# LSN50_v3_0.net
KiCad netlist of a schematic drawn in EAGLE
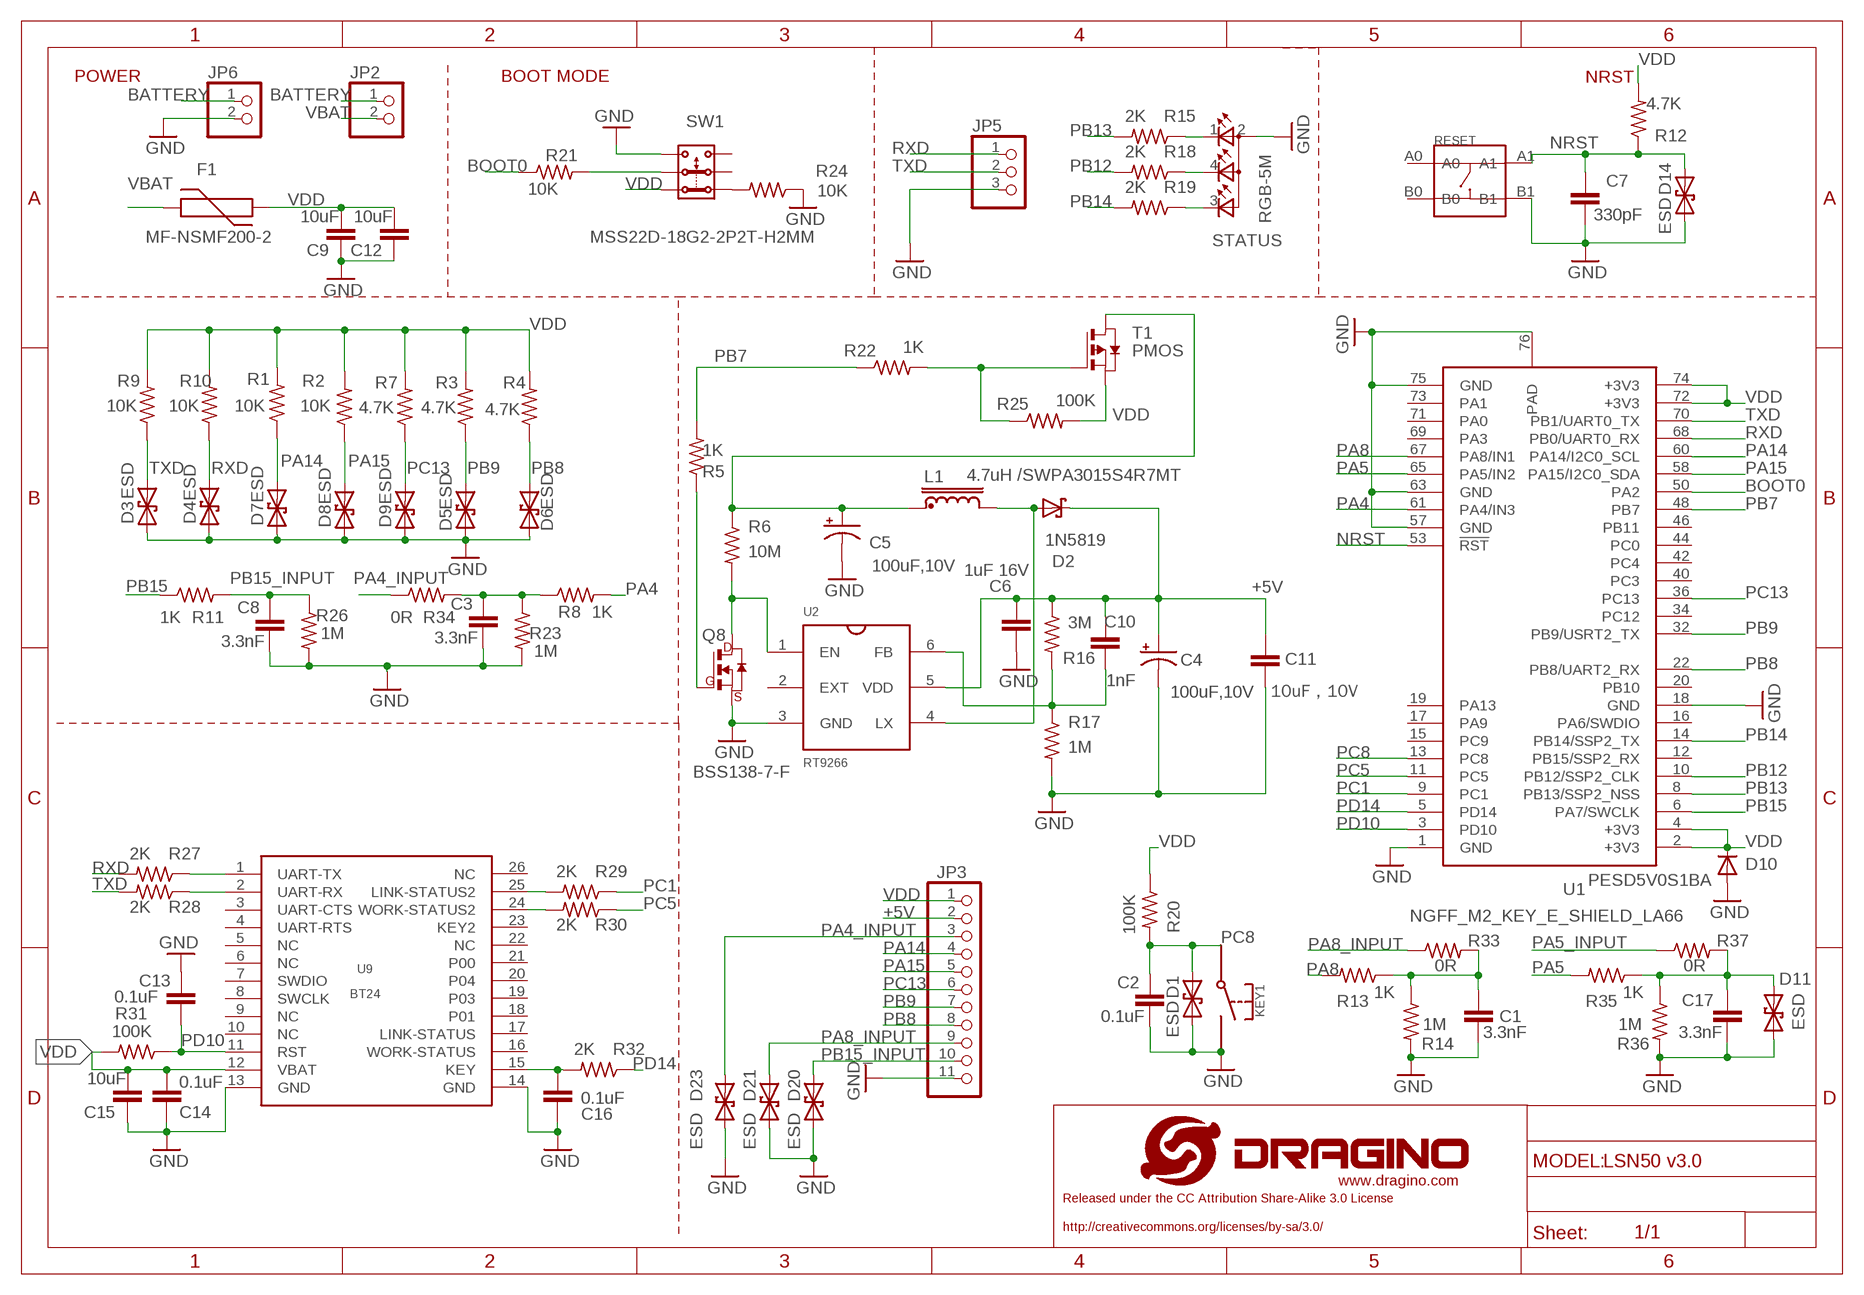
[diagram p0: schematic, sheet 1]

(export (version "E")
  (design (tool "Eeschema 10.0.6"))
  (components
    (comp (ref "C1")
      (value "3.3nF")
      (footprint "eagle-import:C0402")
      (libsource (lib "eagle-import") (part "C-EUC0402"))
    )
    (comp (ref "C2")
      (value "0.1uF")
      (footprint "eagle-import:C0402")
      (libsource (lib "eagle-import") (part "C-EUC0402"))
    )
    (comp (ref "C3")
      (value "3.3nF")
      (footprint "eagle-import:C0402")
      (libsource (lib "eagle-import") (part "C-EUC0402"))
    )
    (comp (ref "C4")
      (value "100uF,10V")
      (footprint "eagle-import:SMC_B")
      (libsource (lib "eagle-import") (part "CPOL-USSMCB"))
    )
    (comp (ref "C5")
      (value "100uF,10V")
      (footprint "eagle-import:SMC_B")
      (libsource (lib "eagle-import") (part "CPOL-USSMCB"))
    )
    (comp (ref "C6")
      (value "1uF 16V")
      (footprint "eagle-import:C0603")
      (libsource (lib "eagle-import") (part "C-EUC0603"))
    )
    (comp (ref "C7")
      (value "330pF")
      (footprint "eagle-import:C0402")
      (libsource (lib "eagle-import") (part "C-EUC0402"))
    )
    (comp (ref "C8")
      (value "3.3nF")
      (footprint "eagle-import:C0402")
      (libsource (lib "eagle-import") (part "C-EUC0402"))
    )
    (comp (ref "C9")
      (value "10uF")
      (footprint "eagle-import:C0805")
      (libsource (lib "eagle-import") (part "C-EUC0805"))
    )
    (comp (ref "C10")
      (value "1nF")
      (footprint "eagle-import:C0402")
      (libsource (lib "eagle-import") (part "C-EUC0402"))
    )
    (comp (ref "C11")
      (value "10uF，10V")
      (footprint "eagle-import:C0805")
      (libsource (lib "eagle-import") (part "dragino-passive_C-EUC0805"))
    )
    (comp (ref "C12")
      (value "10uF")
      (footprint "eagle-import:C0805")
      (libsource (lib "eagle-import") (part "C-EUC0805"))
    )
    (comp (ref "C13")
      (value "0.1uF")
      (footprint "eagle-import:C0402")
      (libsource (lib "eagle-import") (part "C-EUC0402"))
    )
    (comp (ref "C14")
      (value "0.1uF")
      (footprint "eagle-import:C0402")
      (libsource (lib "eagle-import") (part "C-EUC0402"))
    )
    (comp (ref "C15")
      (value "10uF")
      (footprint "eagle-import:C0805")
      (libsource (lib "eagle-import") (part "C-EUC0805"))
    )
    (comp (ref "C16")
      (value "0.1uF")
      (footprint "eagle-import:C0402")
      (libsource (lib "eagle-import") (part "C-EUC0402"))
    )
    (comp (ref "C17")
      (value "3.3nF")
      (footprint "eagle-import:C0402")
      (libsource (lib "eagle-import") (part "C-EUC0402"))
    )
    (comp (ref "D1")
      (value "ESD")
      (footprint "eagle-import:DFN1006")
      (libsource (lib "eagle-import") (part "ESD_TVS"))
    )
    (comp (ref "D2")
      (value "1N5819")
      (footprint "eagle-import:SOD123FL")
      (libsource (lib "eagle-import") (part "SMF5.0AT1"))
    )
    (comp (ref "D3")
      (value "ESD")
      (footprint "eagle-import:DFN1006")
      (libsource (lib "eagle-import") (part "ESD_TVS"))
    )
    (comp (ref "D4")
      (value "ESD")
      (footprint "eagle-import:DFN1006")
      (libsource (lib "eagle-import") (part "ESD_TVS"))
    )
    (comp (ref "D5")
      (value "ESD")
      (footprint "eagle-import:DFN1006")
      (libsource (lib "eagle-import") (part "ESD_TVS"))
    )
    (comp (ref "D6")
      (value "ESD")
      (footprint "eagle-import:DFN1006")
      (libsource (lib "eagle-import") (part "ESD_TVS"))
    )
    (comp (ref "D7")
      (value "ESD")
      (footprint "eagle-import:DFN1006")
      (libsource (lib "eagle-import") (part "ESD_TVS"))
    )
    (comp (ref "D8")
      (value "ESD")
      (footprint "eagle-import:DFN1006")
      (libsource (lib "eagle-import") (part "ESD_TVS"))
    )
    (comp (ref "D9")
      (value "ESD")
      (footprint "eagle-import:DFN1006")
      (libsource (lib "eagle-import") (part "ESD_TVS"))
    )
    (comp (ref "D10")
      (value "PESD5V0S1BA")
      (footprint "eagle-import:DIODE_SOD323-R")
      (libsource (lib "eagle-import") (part "DIODESOD323-R"))
    )
    (comp (ref "D11")
      (value "ESD")
      (footprint "eagle-import:DFN1006")
      (libsource (lib "eagle-import") (part "ESD_TVS"))
    )
    (comp (ref "D14")
      (value "ESD")
      (footprint "eagle-import:DFN1006")
      (libsource (lib "eagle-import") (part "ESD_TVS"))
    )
    (comp (ref "D20")
      (value "ESD")
      (footprint "eagle-import:DFN1006")
      (libsource (lib "eagle-import") (part "ESD_TVS"))
    )
    (comp (ref "D21")
      (value "ESD")
      (footprint "eagle-import:DFN1006")
      (libsource (lib "eagle-import") (part "ESD_TVS"))
    )
    (comp (ref "D23")
      (value "ESD")
      (footprint "eagle-import:DFN1006")
      (libsource (lib "eagle-import") (part "ESD_TVS"))
    )
    (comp (ref "F1")
      (value "MF-NSMF200-2")
      (footprint "eagle-import:R1206")
      (libsource (lib "eagle-import") (part "FUSE1206"))
    )
    (comp (ref "JP2")
      (value "PINHD-1X2")
      (footprint "eagle-import:1X02")
      (libsource (lib "eagle-import") (part "PINHD-1X2"))
    )
    (comp (ref "JP3")
      (value "PINHD-1X11-MM")
      (footprint "eagle-import:KF350-11P")
      (libsource (lib "eagle-import") (part "PINHD-1X11-MM"))
    )
    (comp (ref "JP5")
      (value "PINHD-1X3")
      (footprint "eagle-import:1X03")
      (libsource (lib "eagle-import") (part "PINHD-1X3"))
    )
    (comp (ref "JP6")
      (value "PINHD-1X2\"\"")
      (footprint "eagle-import:XH2.54-2P")
      (libsource (lib "eagle-import") (part "PINHD-1X2{dblquote}{dblquote}"))
    )
    (comp (ref "KEY1")
      (value "SWITCHDIL4")
      (footprint "eagle-import:SWITCH_6X6X19_DIL4")
      (libsource (lib "eagle-import") (part "SWITCHDIL4"))
    )
    (comp (ref "L1")
      (value "4.7uH /SWPA3015S4R7MT")
      (footprint "eagle-import:SWPA3010S")
      (libsource (lib "eagle-import") (part "INDUCTORSWPA3010S"))
    )
    (comp (ref "Q8")
      (value "BSS138-7-F")
      (footprint "eagle-import:SOT-23")
      (libsource (lib "eagle-import") (part "NMOSFET"))
    )
    (comp (ref "R1")
      (value "10K")
      (footprint "eagle-import:R0402")
      (libsource (lib "eagle-import") (part "R-US_R0402"))
    )
    (comp (ref "R2")
      (value "10K")
      (footprint "eagle-import:R0402")
      (libsource (lib "eagle-import") (part "R-US_R0402"))
    )
    (comp (ref "R3")
      (value "4.7K")
      (footprint "eagle-import:R0402")
      (libsource (lib "eagle-import") (part "R-US_R0402"))
    )
    (comp (ref "R4")
      (value "4.7K")
      (footprint "eagle-import:R0402")
      (libsource (lib "eagle-import") (part "R-US_R0402"))
    )
    (comp (ref "R5")
      (value "1K")
      (footprint "eagle-import:R0402")
      (libsource (lib "eagle-import") (part "R-US_R0402"))
    )
    (comp (ref "R6")
      (value "10M")
      (footprint "eagle-import:R0402")
      (libsource (lib "eagle-import") (part "R-US_R0402"))
    )
    (comp (ref "R7")
      (value "4.7K")
      (footprint "eagle-import:R0402")
      (libsource (lib "eagle-import") (part "R-US_R0402"))
    )
    (comp (ref "R8")
      (value "1K")
      (footprint "eagle-import:R0402")
      (libsource (lib "eagle-import") (part "R-US_R0402"))
    )
    (comp (ref "R9")
      (value "10K")
      (footprint "eagle-import:R0402")
      (libsource (lib "eagle-import") (part "R-US_R0402"))
    )
    (comp (ref "R10")
      (value "10K")
      (footprint "eagle-import:R0402")
      (libsource (lib "eagle-import") (part "R-US_R0402"))
    )
    (comp (ref "R11")
      (value "1K")
      (footprint "eagle-import:R0402")
      (libsource (lib "eagle-import") (part "R-US_R0402"))
    )
    (comp (ref "R12")
      (value "4.7K")
      (footprint "eagle-import:R0402")
      (libsource (lib "eagle-import") (part "R-US_R0402"))
    )
    (comp (ref "R13")
      (value "1K")
      (footprint "eagle-import:R0402")
      (libsource (lib "eagle-import") (part "R-US_R0402"))
    )
    (comp (ref "R14")
      (value "1M")
      (footprint "eagle-import:R0402")
      (libsource (lib "eagle-import") (part "R-US_R0402"))
    )
    (comp (ref "R15")
      (value "2K")
      (footprint "eagle-import:R0402")
      (libsource (lib "eagle-import") (part "R-US_R0402"))
    )
    (comp (ref "R16")
      (value "3M")
      (footprint "eagle-import:R0402")
      (libsource (lib "eagle-import") (part "R-US_R0402"))
    )
    (comp (ref "R17")
      (value "1M")
      (footprint "eagle-import:R0402")
      (libsource (lib "eagle-import") (part "R-US_R0402"))
    )
    (comp (ref "R18")
      (value "2K")
      (footprint "eagle-import:R0402")
      (libsource (lib "eagle-import") (part "R-US_R0402"))
    )
    (comp (ref "R19")
      (value "2K")
      (footprint "eagle-import:R0402")
      (libsource (lib "eagle-import") (part "R-US_R0402"))
    )
    (comp (ref "R20")
      (value "100K")
      (footprint "eagle-import:R0402")
      (libsource (lib "eagle-import") (part "R-US_R0402"))
    )
    (comp (ref "R21")
      (value "10K")
      (footprint "eagle-import:R0402")
      (libsource (lib "eagle-import") (part "R-US_R0402"))
    )
    (comp (ref "R22")
      (value "1K")
      (footprint "eagle-import:R0402")
      (libsource (lib "eagle-import") (part "R-US_R0402"))
    )
    (comp (ref "R23")
      (value "1M")
      (footprint "eagle-import:R0402")
      (libsource (lib "eagle-import") (part "R-US_R0402"))
    )
    (comp (ref "R24")
      (value "10K")
      (footprint "eagle-import:R0402")
      (libsource (lib "eagle-import") (part "R-US_R0402"))
    )
    (comp (ref "R25")
      (value "100K")
      (footprint "eagle-import:R0402")
      (libsource (lib "eagle-import") (part "R-US_R0402"))
    )
    (comp (ref "R26")
      (value "1M")
      (footprint "eagle-import:R0402")
      (libsource (lib "eagle-import") (part "R-US_R0402"))
    )
    (comp (ref "R27")
      (value "2K")
      (footprint "eagle-import:R0402")
      (libsource (lib "eagle-import") (part "R-US_R0402"))
    )
    (comp (ref "R28")
      (value "2K")
      (footprint "eagle-import:R0402")
      (libsource (lib "eagle-import") (part "R-US_R0402"))
    )
    (comp (ref "R29")
      (value "2K")
      (footprint "eagle-import:R0402")
      (libsource (lib "eagle-import") (part "R-US_R0402"))
    )
    (comp (ref "R30")
      (value "2K")
      (footprint "eagle-import:R0402")
      (libsource (lib "eagle-import") (part "R-US_R0402"))
    )
    (comp (ref "R31")
      (value "100K")
      (footprint "eagle-import:R0402")
      (libsource (lib "eagle-import") (part "R-US_R0402"))
    )
    (comp (ref "R32")
      (value "2K")
      (footprint "eagle-import:R0402")
      (libsource (lib "eagle-import") (part "R-US_R0402"))
    )
    (comp (ref "R33")
      (value "0R")
      (footprint "eagle-import:R0402")
      (libsource (lib "eagle-import") (part "R-US_R0402"))
    )
    (comp (ref "R34")
      (value "0R")
      (footprint "eagle-import:R0402")
      (libsource (lib "eagle-import") (part "R-US_R0402"))
    )
    (comp (ref "R35")
      (value "1K")
      (footprint "eagle-import:R0402")
      (libsource (lib "eagle-import") (part "R-US_R0402"))
    )
    (comp (ref "R36")
      (value "1M")
      (footprint "eagle-import:R0402")
      (libsource (lib "eagle-import") (part "R-US_R0402"))
    )
    (comp (ref "R37")
      (value "0R")
      (footprint "eagle-import:R0402")
      (libsource (lib "eagle-import") (part "R-US_R0402"))
    )
    (comp (ref "RESET")
      (value "轻触开关3*3*1.5四脚贴片开关")
      (footprint "eagle-import:SW4-SMD-3.35X3.35X1.5MM")
      (libsource (lib "eagle-import") (part "BUTTON-4P-3.3X3.3"))
    )
    (comp (ref "STATUS")
      (value "RGB-5M")
      (footprint "eagle-import:RGB")
      (libsource (lib "eagle-import") (part "RGB-5M"))
    )
    (comp (ref "SW1")
      (value "MSS22D-18G2-2P2T-H2MM")
      (footprint "eagle-import:MSS22D-18G2-2P2T-H2MM-DIL")
      (libsource (lib "eagle-import") (part "MSS22D-18G2-2P2T-H2MM"))
    )
    (comp (ref "T1")
      (value "PMOS")
      (footprint "eagle-import:SOT-23")
      (libsource (lib "eagle-import") (part "PMOSSOT23"))
    )
    (comp (ref "U1")
      (value "NGFF_M2_KEY_E_SHIELD_LA66")
      (footprint "eagle-import:NGFF_M2_KEY_E_SHIELD")
      (libsource (lib "eagle-import") (part "NGFF_M2_KEY_E_SHIELD_LA66"))
    )
    (comp (ref "U2")
      (value "RT9266")
      (footprint "eagle-import:6_SOT-23")
      (libsource (lib "eagle-import") (part "RT9266"))
    )
    (comp (ref "U9")
      (value "BT24")
      (footprint "eagle-import:BT24-SMD26")
      (libsource (lib "eagle-import") (part "BT24"))
    )
  )
  (nets
    (net (code "1") (name "/+5V") (class "Default")
      (node (ref "C10") (pin "2") (pinfunction "2_2") (pintype "passive"))
      (node (ref "C11") (pin "2") (pinfunction "2_2") (pintype "passive"))
      (node (ref "C4") (pin "+") (pinfunction "+_+") (pintype "passive"))
      (node (ref "C6") (pin "2") (pinfunction "2_2") (pintype "passive"))
      (node (ref "D2") (pin "C") (pinfunction "C_C") (pintype "passive"))
      (node (ref "JP3") (pin "2") (pinfunction "2_2") (pintype "passive"))
      (node (ref "R16") (pin "1") (pinfunction "1_1") (pintype "passive"))
      (node (ref "U2") (pin "5") (pinfunction "VDD_5") (pintype "bidirectional"))
    )
    (net (code "2") (name "/BATTERY") (class "Default")
      (node (ref "JP2") (pin "1") (pinfunction "1_1") (pintype "passive"))
      (node (ref "JP6") (pin "1") (pinfunction "1_1") (pintype "passive"))
    )
    (net (code "3") (name "/BOOT0") (class "Default")
      (node (ref "R21") (pin "1") (pinfunction "1_1") (pintype "passive"))
      (node (ref "U1") (pin "50") (pinfunction "PA2_50") (pintype "bidirectional"))
    )
    (net (code "4") (name "/NRST") (class "Default")
      (node (ref "C7") (pin "2") (pinfunction "2_2") (pintype "passive"))
      (node (ref "D14") (pin "2") (pinfunction "2_2") (pintype "passive"))
      (node (ref "R12") (pin "1") (pinfunction "1_1") (pintype "passive"))
      (node (ref "RESET") (pin "A1") (pinfunction "A1_A1") (pintype "bidirectional"))
      (node (ref "U1") (pin "53") (pinfunction "~{RST}_53") (pintype "bidirectional"))
    )
    (net (code "5") (name "/PA4") (class "Default")
      (node (ref "R8") (pin "2") (pinfunction "2_2") (pintype "passive"))
      (node (ref "U1") (pin "61") (pinfunction "PA4/IN3_61") (pintype "bidirectional"))
    )
    (net (code "6") (name "/PA4_INPUT") (class "Default")
      (node (ref "D23") (pin "2") (pinfunction "2_2") (pintype "passive"))
      (node (ref "JP3") (pin "3") (pinfunction "3_3") (pintype "passive"))
      (node (ref "R34") (pin "1") (pinfunction "1_1") (pintype "passive"))
    )
    (net (code "7") (name "/PA5") (class "Default")
      (node (ref "R35") (pin "2") (pinfunction "2_2") (pintype "passive"))
      (node (ref "U1") (pin "65") (pinfunction "PA5/IN2_65") (pintype "bidirectional"))
    )
    (net (code "8") (name "/PA5_INPUT") (class "Default")
      (node (ref "R37") (pin "1") (pinfunction "1_1") (pintype "passive"))
    )
    (net (code "9") (name "/PA8") (class "Default")
      (node (ref "R13") (pin "2") (pinfunction "2_2") (pintype "passive"))
      (node (ref "U1") (pin "67") (pinfunction "PA8/IN1_67") (pintype "bidirectional"))
    )
    (net (code "10") (name "/PA8_INPUT") (class "Default")
      (node (ref "D21") (pin "2") (pinfunction "2_2") (pintype "passive"))
      (node (ref "JP3") (pin "9") (pinfunction "9_9") (pintype "passive"))
      (node (ref "R33") (pin "1") (pinfunction "1_1") (pintype "passive"))
    )
    (net (code "11") (name "/PA14") (class "Default")
      (node (ref "D7") (pin "2") (pinfunction "2_2") (pintype "passive"))
      (node (ref "JP3") (pin "4") (pinfunction "4_4") (pintype "passive"))
      (node (ref "R1") (pin "1") (pinfunction "1_1") (pintype "passive"))
      (node (ref "U1") (pin "60") (pinfunction "PA14/I2C0_SCL_60") (pintype "bidirectional"))
    )
    (net (code "12") (name "/PA15") (class "Default")
      (node (ref "D8") (pin "2") (pinfunction "2_2") (pintype "passive"))
      (node (ref "JP3") (pin "5") (pinfunction "5_5") (pintype "passive"))
      (node (ref "R2") (pin "1") (pinfunction "1_1") (pintype "passive"))
      (node (ref "U1") (pin "58") (pinfunction "PA15/I2C0_SDA_58") (pintype "bidirectional"))
    )
    (net (code "13") (name "/PB7") (class "Default")
      (node (ref "R22") (pin "1") (pinfunction "1_1") (pintype "passive"))
      (node (ref "R5") (pin "2") (pinfunction "2_2") (pintype "passive"))
      (node (ref "U1") (pin "48") (pinfunction "PB7_48") (pintype "bidirectional"))
    )
    (net (code "14") (name "/PB8") (class "Default")
      (node (ref "D6") (pin "2") (pinfunction "2_2") (pintype "passive"))
      (node (ref "JP3") (pin "8") (pinfunction "8_8") (pintype "passive"))
      (node (ref "R4") (pin "1") (pinfunction "1_1") (pintype "passive"))
      (node (ref "U1") (pin "22") (pinfunction "PB8/UART2_RX_22") (pintype "bidirectional"))
    )
    (net (code "15") (name "/PB9") (class "Default")
      (node (ref "D5") (pin "2") (pinfunction "2_2") (pintype "passive"))
      (node (ref "JP3") (pin "7") (pinfunction "7_7") (pintype "passive"))
      (node (ref "R3") (pin "1") (pinfunction "1_1") (pintype "passive"))
      (node (ref "U1") (pin "32") (pinfunction "PB9/USRT2_TX_32") (pintype "bidirectional"))
    )
    (net (code "16") (name "/PB12") (class "Default")
      (node (ref "R18") (pin "2") (pinfunction "2_2") (pintype "passive"))
      (node (ref "U1") (pin "10") (pinfunction "PB12/SSP2_CLK_10") (pintype "bidirectional"))
    )
    (net (code "17") (name "/PB13") (class "Default")
      (node (ref "R15") (pin "2") (pinfunction "2_2") (pintype "passive"))
      (node (ref "U1") (pin "8") (pinfunction "PB13/SSP2_NSS_8") (pintype "bidirectional"))
    )
    (net (code "18") (name "/PB14") (class "Default")
      (node (ref "R19") (pin "2") (pinfunction "2_2") (pintype "passive"))
      (node (ref "U1") (pin "14") (pinfunction "PB14/SSP2_TX_14") (pintype "bidirectional"))
    )
    (net (code "19") (name "/PB15") (class "Default")
      (node (ref "R11") (pin "1") (pinfunction "1_1") (pintype "passive"))
      (node (ref "U1") (pin "6") (pinfunction "PA7/SWCLK_6") (pintype "bidirectional"))
    )
    (net (code "20") (name "/PB15_INPUT") (class "Default")
      (node (ref "C8") (pin "2") (pinfunction "2_2") (pintype "passive"))
      (node (ref "D20") (pin "2") (pinfunction "2_2") (pintype "passive"))
      (node (ref "JP3") (pin "10") (pinfunction "10_10") (pintype "passive"))
      (node (ref "R11") (pin "2") (pinfunction "2_2") (pintype "passive"))
      (node (ref "R26") (pin "1") (pinfunction "1_1") (pintype "passive"))
    )
    (net (code "21") (name "/PC1") (class "Default")
      (node (ref "R29") (pin "1") (pinfunction "1_1") (pintype "passive"))
      (node (ref "U1") (pin "9") (pinfunction "PC1_9") (pintype "bidirectional"))
    )
    (net (code "22") (name "/PC5") (class "Default")
      (node (ref "R30") (pin "1") (pinfunction "1_1") (pintype "passive"))
      (node (ref "U1") (pin "11") (pinfunction "PC5_11") (pintype "bidirectional"))
    )
    (net (code "23") (name "/PC8") (class "Default")
      (node (ref "C2") (pin "2") (pinfunction "2_2") (pintype "passive"))
      (node (ref "D1") (pin "2") (pinfunction "2_2") (pintype "passive"))
      (node (ref "KEY1") (pin "1") (pinfunction "P$1_1") (pintype "bidirectional"))
      (node (ref "R20") (pin "2") (pinfunction "2_2") (pintype "passive"))
      (node (ref "U1") (pin "13") (pinfunction "PC8_13") (pintype "bidirectional"))
    )
    (net (code "24") (name "/PC13") (class "Default")
      (node (ref "D9") (pin "2") (pinfunction "2_2") (pintype "passive"))
      (node (ref "JP3") (pin "6") (pinfunction "6_6") (pintype "passive"))
      (node (ref "R7") (pin "1") (pinfunction "1_1") (pintype "passive"))
      (node (ref "U1") (pin "36") (pinfunction "PC13_36") (pintype "bidirectional"))
    )
    (net (code "25") (name "/PD10") (class "Default")
      (node (ref "C13") (pin "1") (pinfunction "1_1") (pintype "passive"))
      (node (ref "R31") (pin "1") (pinfunction "1_1") (pintype "passive"))
      (node (ref "U1") (pin "3") (pinfunction "PD10_3") (pintype "bidirectional"))
      (node (ref "U9") (pin "11") (pinfunction "RST_11") (pintype "bidirectional"))
    )
    (net (code "26") (name "/PD14") (class "Default")
      (node (ref "R32") (pin "1") (pinfunction "1_1") (pintype "passive"))
      (node (ref "U1") (pin "5") (pinfunction "PD14_5") (pintype "bidirectional"))
    )
    (net (code "27") (name "/RXD") (class "Default")
      (node (ref "D4") (pin "2") (pinfunction "2_2") (pintype "passive"))
      (node (ref "JP5") (pin "1") (pinfunction "1_1") (pintype "passive"))
      (node (ref "R10") (pin "1") (pinfunction "1_1") (pintype "passive"))
      (node (ref "R27") (pin "2") (pinfunction "2_2") (pintype "passive"))
      (node (ref "U1") (pin "68") (pinfunction "PB0/UART0_RX_68") (pintype "bidirectional"))
    )
    (net (code "28") (name "/TXD") (class "Default")
      (node (ref "D3") (pin "2") (pinfunction "2_2") (pintype "passive"))
      (node (ref "JP5") (pin "2") (pinfunction "2_2") (pintype "passive"))
      (node (ref "R28") (pin "2") (pinfunction "2_2") (pintype "passive"))
      (node (ref "R9") (pin "1") (pinfunction "1_1") (pintype "passive"))
      (node (ref "U1") (pin "70") (pinfunction "PB1/UART0_TX_70") (pintype "bidirectional"))
    )
    (net (code "29") (name "/VBAT") (class "Default")
      (node (ref "F1") (pin "2") (pinfunction "2_2") (pintype "passive"))
      (node (ref "JP2") (pin "2") (pinfunction "2_2") (pintype "passive"))
    )
    (net (code "30") (name "GND") (class "Default")
      (node (ref "C1") (pin "1") (pinfunction "1_1") (pintype "passive"))
      (node (ref "C11") (pin "1") (pinfunction "1_1") (pintype "passive"))
      (node (ref "C12") (pin "1") (pinfunction "1_1") (pintype "passive"))
      (node (ref "C13") (pin "2") (pinfunction "2_2") (pintype "passive"))
      (node (ref "C14") (pin "2") (pinfunction "2_2") (pintype "passive"))
      (node (ref "C15") (pin "1") (pinfunction "1_1") (pintype "passive"))
      (node (ref "C16") (pin "2") (pinfunction "2_2") (pintype "passive"))
      (node (ref "C17") (pin "1") (pinfunction "1_1") (pintype "passive"))
      (node (ref "C2") (pin "1") (pinfunction "1_1") (pintype "passive"))
      (node (ref "C3") (pin "1") (pinfunction "1_1") (pintype "passive"))
      (node (ref "C4") (pin "-") (pinfunction "-_-") (pintype "passive"))
      (node (ref "C5") (pin "-") (pinfunction "-_-") (pintype "passive"))
      (node (ref "C6") (pin "1") (pinfunction "1_1") (pintype "passive"))
      (node (ref "C7") (pin "1") (pinfunction "1_1") (pintype "passive"))
      (node (ref "C8") (pin "1") (pinfunction "1_1") (pintype "passive"))
      (node (ref "C9") (pin "1") (pinfunction "1_1") (pintype "passive"))
      (node (ref "D1") (pin "1") (pinfunction "1_1") (pintype "passive"))
      (node (ref "D10") (pin "A") (pinfunction "A_A") (pintype "passive"))
      (node (ref "D11") (pin "1") (pinfunction "1_1") (pintype "passive"))
      (node (ref "D14") (pin "1") (pinfunction "1_1") (pintype "passive"))
      (node (ref "D20") (pin "1") (pinfunction "1_1") (pintype "passive"))
      (node (ref "D21") (pin "1") (pinfunction "1_1") (pintype "passive"))
      (node (ref "D23") (pin "1") (pinfunction "1_1") (pintype "passive"))
      (node (ref "D3") (pin "1") (pinfunction "1_1") (pintype "passive"))
      (node (ref "D4") (pin "1") (pinfunction "1_1") (pintype "passive"))
      (node (ref "D5") (pin "1") (pinfunction "1_1") (pintype "passive"))
      (node (ref "D6") (pin "1") (pinfunction "1_1") (pintype "passive"))
      (node (ref "D7") (pin "1") (pinfunction "1_1") (pintype "passive"))
      (node (ref "D8") (pin "1") (pinfunction "1_1") (pintype "passive"))
      (node (ref "D9") (pin "1") (pinfunction "1_1") (pintype "passive"))
      (node (ref "JP3") (pin "11") (pinfunction "11_11") (pintype "passive"))
      (node (ref "JP5") (pin "3") (pinfunction "3_3") (pintype "passive"))
      (node (ref "JP6") (pin "2") (pinfunction "2_2") (pintype "passive"))
      (node (ref "KEY1") (pin "2") (pinfunction "P$2_2") (pintype "bidirectional"))
      (node (ref "Q8") (pin "2") (pinfunction "S_2") (pintype "passive"))
      (node (ref "R14") (pin "2") (pinfunction "2_2") (pintype "passive"))
      (node (ref "R17") (pin "2") (pinfunction "2_2") (pintype "passive"))
      (node (ref "R23") (pin "2") (pinfunction "2_2") (pintype "passive"))
      (node (ref "R24") (pin "1") (pinfunction "1_1") (pintype "passive"))
      (node (ref "R26") (pin "2") (pinfunction "2_2") (pintype "passive"))
      (node (ref "R36") (pin "2") (pinfunction "2_2") (pintype "passive"))
      (node (ref "RESET") (pin "B1") (pinfunction "B1_B1") (pintype "bidirectional"))
      (node (ref "STATUS") (pin "2") (pinfunction "A_2") (pintype "passive"))
      (node (ref "SW1") (pin "1") (pinfunction "1_1") (pintype "bidirectional"))
      (node (ref "U1") (pin "1") (pinfunction "GND_1") (pintype "bidirectional"))
      (node (ref "U1") (pin "18") (pinfunction "GND_18") (pintype "bidirectional"))
      (node (ref "U1") (pin "57") (pinfunction "GND_57") (pintype "bidirectional"))
      (node (ref "U1") (pin "63") (pinfunction "GND_63") (pintype "bidirectional"))
      (node (ref "U1") (pin "75") (pinfunction "GND_75") (pintype "bidirectional"))
      (node (ref "U1") (pin "76") (pinfunction "PAD_76") (pintype "bidirectional"))
      (node (ref "U2") (pin "3") (pinfunction "GND_3") (pintype "bidirectional"))
      (node (ref "U9") (pin "13") (pinfunction "GND_13") (pintype "bidirectional"))
      (node (ref "U9") (pin "14") (pinfunction "GND_14") (pintype "bidirectional"))
    )
    (net (code "31") (name "Net-(C1-Pad2)") (class "Default")
      (node (ref "C1") (pin "2") (pinfunction "2_2") (pintype "passive"))
      (node (ref "R13") (pin "1") (pinfunction "1_1") (pintype "passive"))
      (node (ref "R14") (pin "1") (pinfunction "1_1") (pintype "passive"))
      (node (ref "R33") (pin "2") (pinfunction "2_2") (pintype "passive"))
    )
    (net (code "32") (name "Net-(C3-Pad2)") (class "Default")
      (node (ref "C3") (pin "2") (pinfunction "2_2") (pintype "passive"))
      (node (ref "R23") (pin "1") (pinfunction "1_1") (pintype "passive"))
      (node (ref "R34") (pin "2") (pinfunction "2_2") (pintype "passive"))
      (node (ref "R8") (pin "1") (pinfunction "1_1") (pintype "passive"))
    )
    (net (code "33") (name "Net-(C17-Pad2)") (class "Default")
      (node (ref "C17") (pin "2") (pinfunction "2_2") (pintype "passive"))
      (node (ref "D11") (pin "2") (pinfunction "2_2") (pintype "passive"))
      (node (ref "R35") (pin "1") (pinfunction "1_1") (pintype "passive"))
      (node (ref "R36") (pin "1") (pinfunction "1_1") (pintype "passive"))
      (node (ref "R37") (pin "2") (pinfunction "2_2") (pintype "passive"))
    )
    (net (code "34") (name "Net-(L1-1)") (class "Default")
      (node (ref "C5") (pin "+") (pinfunction "+_+") (pintype "passive"))
      (node (ref "L1") (pin "P$1") (pinfunction "1_P$1") (pintype "passive"))
      (node (ref "R6") (pin "1") (pinfunction "1_1") (pintype "passive"))
      (node (ref "T1") (pin "1") (pinfunction "D_1") (pintype "passive"))
    )
    (net (code "35") (name "Net-(L1-4)") (class "Default")
      (node (ref "D2") (pin "A") (pinfunction "A_A") (pintype "passive"))
      (node (ref "L1") (pin "P$2") (pinfunction "4_P$2") (pintype "passive"))
      (node (ref "U2") (pin "4") (pinfunction "LX_4") (pintype "bidirectional"))
    )
    (net (code "36") (name "Net-(Q8-D)") (class "Default")
      (node (ref "Q8") (pin "1") (pinfunction "D_1") (pintype "passive"))
      (node (ref "R6") (pin "2") (pinfunction "2_2") (pintype "passive"))
      (node (ref "U2") (pin "1") (pinfunction "EN_1") (pintype "input"))
    )
    (net (code "37") (name "Net-(Q8-G)") (class "Default")
      (node (ref "Q8") (pin "3") (pinfunction "G_3") (pintype "passive"))
      (node (ref "R5") (pin "1") (pinfunction "1_1") (pintype "passive"))
    )
    (net (code "38") (name "Net-(R21-Pad2)") (class "Default")
      (node (ref "R21") (pin "2") (pinfunction "2_2") (pintype "passive"))
      (node (ref "SW1") (pin "2") (pinfunction "2_2") (pintype "bidirectional"))
    )
    (net (code "39") (name "Net-(R24-Pad2)") (class "Default")
      (node (ref "R24") (pin "2") (pinfunction "2_2") (pintype "passive"))
      (node (ref "SW1") (pin "4") (pinfunction "4_4") (pintype "bidirectional"))
    )
    (net (code "40") (name "Net-(STATUS-CBLUE)") (class "Default")
      (node (ref "R18") (pin "1") (pinfunction "1_1") (pintype "passive"))
      (node (ref "STATUS") (pin "4") (pinfunction "CBLUE_4") (pintype "passive"))
    )
    (net (code "41") (name "Net-(STATUS-CGREEN)") (class "Default")
      (node (ref "R19") (pin "1") (pinfunction "1_1") (pintype "passive"))
      (node (ref "STATUS") (pin "3") (pinfunction "CGREEN_3") (pintype "passive"))
    )
    (net (code "42") (name "Net-(STATUS-CRED)") (class "Default")
      (node (ref "R15") (pin "1") (pinfunction "1_1") (pintype "passive"))
      (node (ref "STATUS") (pin "1") (pinfunction "CRED_1") (pintype "passive"))
    )
    (net (code "43") (name "Net-(T1-G)") (class "Default")
      (node (ref "R22") (pin "2") (pinfunction "2_2") (pintype "passive"))
      (node (ref "R25") (pin "1") (pinfunction "1_1") (pintype "passive"))
      (node (ref "T1") (pin "3") (pinfunction "G_3") (pintype "passive"))
    )
    (net (code "44") (name "Net-(U2-FB)") (class "Default")
      (node (ref "C10") (pin "1") (pinfunction "1_1") (pintype "passive"))
      (node (ref "R16") (pin "2") (pinfunction "2_2") (pintype "passive"))
      (node (ref "R17") (pin "1") (pinfunction "1_1") (pintype "passive"))
      (node (ref "U2") (pin "6") (pinfunction "FB_6") (pintype "bidirectional"))
    )
    (net (code "45") (name "Net-(U9-KEY)") (class "Default")
      (node (ref "C16") (pin "1") (pinfunction "1_1") (pintype "passive"))
      (node (ref "R32") (pin "2") (pinfunction "2_2") (pintype "passive"))
      (node (ref "U9") (pin "15") (pinfunction "KEY_15") (pintype "bidirectional"))
    )
    (net (code "46") (name "Net-(U9-LINK-STATUS2)") (class "Default")
      (node (ref "R29") (pin "2") (pinfunction "2_2") (pintype "passive"))
      (node (ref "U9") (pin "25") (pinfunction "LINK-STATUS2_25") (pintype "input"))
    )
    (net (code "47") (name "Net-(U9-UART-RX)") (class "Default")
      (node (ref "R28") (pin "1") (pinfunction "1_1") (pintype "passive"))
      (node (ref "U9") (pin "2") (pinfunction "UART-RX_2") (pintype "bidirectional"))
    )
    (net (code "48") (name "Net-(U9-UART-TX)") (class "Default")
      (node (ref "R27") (pin "1") (pinfunction "1_1") (pintype "passive"))
      (node (ref "U9") (pin "1") (pinfunction "UART-TX_1") (pintype "bidirectional"))
    )
    (net (code "49") (name "Net-(U9-WORK-STATUS2)") (class "Default")
      (node (ref "R30") (pin "2") (pinfunction "2_2") (pintype "passive"))
      (node (ref "U9") (pin "24") (pinfunction "WORK-STATUS2_24") (pintype "input"))
    )
    (net (code "50") (name "VDD") (class "Default")
      (node (ref "C12") (pin "2") (pinfunction "2_2") (pintype "passive"))
      (node (ref "C14") (pin "1") (pinfunction "1_1") (pintype "passive"))
      (node (ref "C15") (pin "2") (pinfunction "2_2") (pintype "passive"))
      (node (ref "C9") (pin "2") (pinfunction "2_2") (pintype "passive"))
      (node (ref "D10") (pin "C") (pinfunction "C_C") (pintype "passive"))
      (node (ref "F1") (pin "1") (pinfunction "1_1") (pintype "passive"))
      (node (ref "JP3") (pin "1") (pinfunction "1_1") (pintype "passive"))
      (node (ref "R1") (pin "2") (pinfunction "2_2") (pintype "passive"))
      (node (ref "R10") (pin "2") (pinfunction "2_2") (pintype "passive"))
      (node (ref "R12") (pin "2") (pinfunction "2_2") (pintype "passive"))
      (node (ref "R2") (pin "2") (pinfunction "2_2") (pintype "passive"))
      (node (ref "R20") (pin "1") (pinfunction "1_1") (pintype "passive"))
      (node (ref "R25") (pin "2") (pinfunction "2_2") (pintype "passive"))
      (node (ref "R3") (pin "2") (pinfunction "2_2") (pintype "passive"))
      (node (ref "R31") (pin "2") (pinfunction "2_2") (pintype "passive"))
      (node (ref "R4") (pin "2") (pinfunction "2_2") (pintype "passive"))
      (node (ref "R7") (pin "2") (pinfunction "2_2") (pintype "passive"))
      (node (ref "R9") (pin "2") (pinfunction "2_2") (pintype "passive"))
      (node (ref "SW1") (pin "3") (pinfunction "3_3") (pintype "bidirectional"))
      (node (ref "T1") (pin "2") (pinfunction "S_2") (pintype "passive"))
      (node (ref "U1") (pin "2") (pinfunction "+3V3_2") (pintype "bidirectional"))
      (node (ref "U1") (pin "4") (pinfunction "+3V3_4") (pintype "bidirectional"))
      (node (ref "U1") (pin "72") (pinfunction "+3V3_72") (pintype "bidirectional"))
      (node (ref "U1") (pin "74") (pinfunction "+3V3_74") (pintype "bidirectional"))
      (node (ref "U9") (pin "12") (pinfunction "VBAT_12") (pintype "bidirectional"))
    )
    (net (code "51") (name "unconnected-(RESET-PadA0)") (class "Default")
      (node (ref "RESET") (pin "A0") (pinfunction "A0_A0") (pintype "bidirectional"))
    )
    (net (code "52") (name "unconnected-(RESET-PadB0)") (class "Default")
      (node (ref "RESET") (pin "B0") (pinfunction "B0_B0") (pintype "bidirectional"))
    )
    (net (code "53") (name "unconnected-(SW1-Pad5)") (class "Default")
      (node (ref "SW1") (pin "5") (pinfunction "5_5") (pintype "bidirectional"))
    )
    (net (code "54") (name "unconnected-(SW1-Pad6)") (class "Default")
      (node (ref "SW1") (pin "6") (pinfunction "6_6") (pintype "bidirectional"))
    )
    (net (code "55") (name "unconnected-(U1-PA0-Pad71)") (class "Default")
      (node (ref "U1") (pin "71") (pinfunction "PA0_71") (pintype "bidirectional"))
    )
    (net (code "56") (name "unconnected-(U1-PA1-Pad73)") (class "Default")
      (node (ref "U1") (pin "73") (pinfunction "PA1_73") (pintype "bidirectional"))
    )
    (net (code "57") (name "unconnected-(U1-PA3-Pad69)") (class "Default")
      (node (ref "U1") (pin "69") (pinfunction "PA3_69") (pintype "bidirectional"))
    )
    (net (code "58") (name "unconnected-(U1-PA6{slash}SWDIO-Pad16)") (class "Default")
      (node (ref "U1") (pin "16") (pinfunction "PA6/SWDIO_16") (pintype "bidirectional"))
    )
    (net (code "59") (name "unconnected-(U1-PA9-Pad17)") (class "Default")
      (node (ref "U1") (pin "17") (pinfunction "PA9_17") (pintype "bidirectional"))
    )
    (net (code "60") (name "unconnected-(U1-PA13-Pad19)") (class "Default")
      (node (ref "U1") (pin "19") (pinfunction "PA13_19") (pintype "bidirectional"))
    )
    (net (code "61") (name "unconnected-(U1-PB10-Pad20)") (class "Default")
      (node (ref "U1") (pin "20") (pinfunction "PB10_20") (pintype "bidirectional"))
    )
    (net (code "62") (name "unconnected-(U1-PB11-Pad46)") (class "Default")
      (node (ref "U1") (pin "46") (pinfunction "PB11_46") (pintype "bidirectional"))
    )
    (net (code "63") (name "unconnected-(U1-PB15{slash}SSP2_RX-Pad12)") (class "Default")
      (node (ref "U1") (pin "12") (pinfunction "PB15/SSP2_RX_12") (pintype "bidirectional"))
    )
    (net (code "64") (name "unconnected-(U1-PC0-Pad44)") (class "Default")
      (node (ref "U1") (pin "44") (pinfunction "PC0_44") (pintype "bidirectional"))
    )
    (net (code "65") (name "unconnected-(U1-PC3-Pad40)") (class "Default")
      (node (ref "U1") (pin "40") (pinfunction "PC3_40") (pintype "bidirectional"))
    )
    (net (code "66") (name "unconnected-(U1-PC4-Pad42)") (class "Default")
      (node (ref "U1") (pin "42") (pinfunction "PC4_42") (pintype "bidirectional"))
    )
    (net (code "67") (name "unconnected-(U1-PC9-Pad15)") (class "Default")
      (node (ref "U1") (pin "15") (pinfunction "PC9_15") (pintype "bidirectional"))
    )
    (net (code "68") (name "unconnected-(U1-PC12-Pad34)") (class "Default")
      (node (ref "U1") (pin "34") (pinfunction "PC12_34") (pintype "bidirectional"))
    )
    (net (code "69") (name "unconnected-(U2-EXT-Pad2)") (class "Default")
      (node (ref "U2") (pin "2") (pinfunction "EXT_2") (pintype "bidirectional"))
    )
    (net (code "70") (name "unconnected-(U9-KEY2-Pad23)") (class "Default")
      (node (ref "U9") (pin "23") (pinfunction "KEY2_23") (pintype "input"))
    )
    (net (code "71") (name "unconnected-(U9-LINK-STATUS-Pad17)") (class "Default")
      (node (ref "U9") (pin "17") (pinfunction "LINK-STATUS_17") (pintype "bidirectional"))
    )
    (net (code "72") (name "unconnected-(U9-NC-Pad5)") (class "Default")
      (node (ref "U9") (pin "5") (pinfunction "NC_5") (pintype "bidirectional"))
    )
    (net (code "73") (name "unconnected-(U9-NC-Pad6)") (class "Default")
      (node (ref "U9") (pin "6") (pinfunction "NC_6") (pintype "bidirectional"))
    )
    (net (code "74") (name "unconnected-(U9-NC-Pad9)") (class "Default")
      (node (ref "U9") (pin "9") (pinfunction "NC_9") (pintype "bidirectional"))
    )
    (net (code "75") (name "unconnected-(U9-NC-Pad10)") (class "Default")
      (node (ref "U9") (pin "10") (pinfunction "NC_10") (pintype "bidirectional"))
    )
    (net (code "76") (name "unconnected-(U9-NC-Pad22)") (class "Default")
      (node (ref "U9") (pin "22") (pinfunction "NC_22") (pintype "input"))
    )
    (net (code "77") (name "unconnected-(U9-NC-Pad26)") (class "Default")
      (node (ref "U9") (pin "26") (pinfunction "NC_26") (pintype "input"))
    )
    (net (code "78") (name "unconnected-(U9-P00-Pad21)") (class "Default")
      (node (ref "U9") (pin "21") (pinfunction "P00_21") (pintype "bidirectional"))
    )
    (net (code "79") (name "unconnected-(U9-P01-Pad18)") (class "Default")
      (node (ref "U9") (pin "18") (pinfunction "P01_18") (pintype "bidirectional"))
    )
    (net (code "80") (name "unconnected-(U9-P03-Pad19)") (class "Default")
      (node (ref "U9") (pin "19") (pinfunction "P03_19") (pintype "bidirectional"))
    )
    (net (code "81") (name "unconnected-(U9-P04-Pad20)") (class "Default")
      (node (ref "U9") (pin "20") (pinfunction "P04_20") (pintype "bidirectional"))
    )
    (net (code "82") (name "unconnected-(U9-SWCLK-Pad8)") (class "Default")
      (node (ref "U9") (pin "8") (pinfunction "SWCLK_8") (pintype "input"))
    )
    (net (code "83") (name "unconnected-(U9-SWDIO-Pad7)") (class "Default")
      (node (ref "U9") (pin "7") (pinfunction "SWDIO_7") (pintype "bidirectional"))
    )
    (net (code "84") (name "unconnected-(U9-UART-CTS-Pad3)") (class "Default")
      (node (ref "U9") (pin "3") (pinfunction "UART-CTS_3") (pintype "bidirectional"))
    )
    (net (code "85") (name "unconnected-(U9-UART-RTS-Pad4)") (class "Default")
      (node (ref "U9") (pin "4") (pinfunction "UART-RTS_4") (pintype "bidirectional"))
    )
    (net (code "86") (name "unconnected-(U9-WORK-STATUS-Pad16)") (class "Default")
      (node (ref "U9") (pin "16") (pinfunction "WORK-STATUS_16") (pintype "bidirectional"))
    )
  )
)
